# Preamp_Prueba.net
KiCad netlist of a schematic drawn in EAGLE
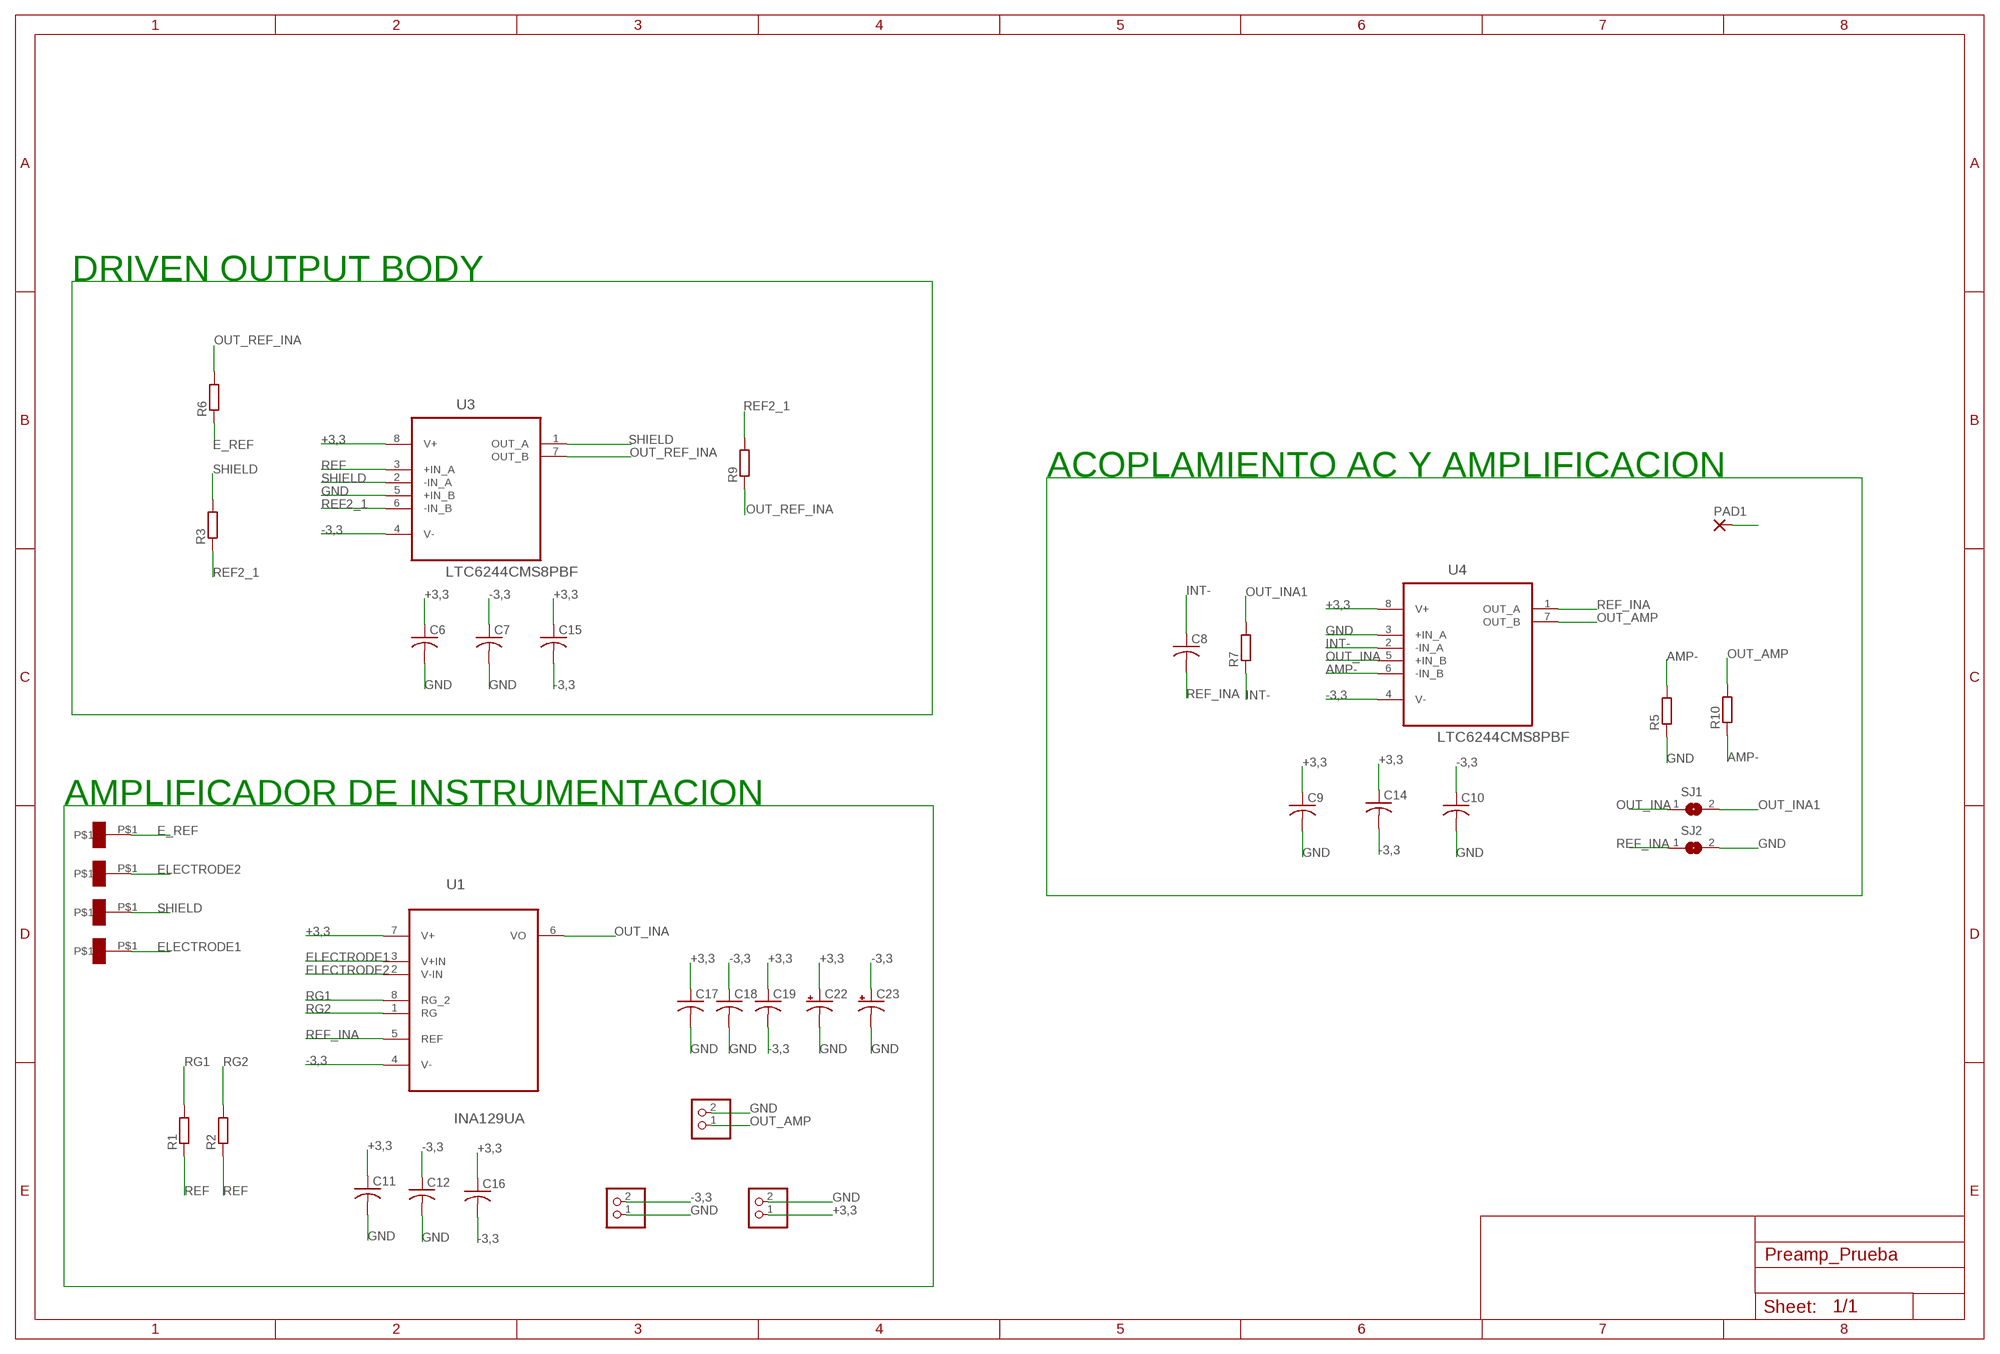
[diagram p0: schematic, sheet 1]

(export (version "E")
  (design (tool "Eeschema 10.0.6"))
  (components
    (comp (ref "C6")
      (value "C-USC0805")
      (footprint "eagle-import:C0805")
      (libsource (lib "eagle-import") (part "C-USC0805"))
    )
    (comp (ref "C7")
      (value "C-USC0805")
      (footprint "eagle-import:C0805")
      (libsource (lib "eagle-import") (part "C-USC0805"))
    )
    (comp (ref "C8")
      (value "C-USC0805")
      (footprint "eagle-import:C0805")
      (libsource (lib "eagle-import") (part "C-USC0805"))
    )
    (comp (ref "C9")
      (value "C-USC0805")
      (footprint "eagle-import:C0805")
      (libsource (lib "eagle-import") (part "C-USC0805"))
    )
    (comp (ref "C10")
      (value "C-USC0805")
      (footprint "eagle-import:C0805")
      (libsource (lib "eagle-import") (part "C-USC0805"))
    )
    (comp (ref "C11")
      (value "C-USC0805")
      (footprint "eagle-import:C0805")
      (libsource (lib "eagle-import") (part "C-USC0805"))
    )
    (comp (ref "C12")
      (value "C-USC0805")
      (footprint "eagle-import:C0805")
      (libsource (lib "eagle-import") (part "C-USC0805"))
    )
    (comp (ref "C14")
      (value "C-USC0805")
      (footprint "eagle-import:C0805")
      (libsource (lib "eagle-import") (part "C-USC0805"))
    )
    (comp (ref "C15")
      (value "C-USC0805")
      (footprint "eagle-import:C0805")
      (libsource (lib "eagle-import") (part "C-USC0805"))
    )
    (comp (ref "C16")
      (value "C-USC0805")
      (footprint "eagle-import:C0805")
      (libsource (lib "eagle-import") (part "C-USC0805"))
    )
    (comp (ref "C17")
      (value "C-USC0805")
      (footprint "eagle-import:C0805")
      (libsource (lib "eagle-import") (part "C-USC0805"))
    )
    (comp (ref "C18")
      (value "C-USC0805")
      (footprint "eagle-import:C0805")
      (libsource (lib "eagle-import") (part "C-USC0805"))
    )
    (comp (ref "C19")
      (value "C-USC0805")
      (footprint "eagle-import:C0805")
      (libsource (lib "eagle-import") (part "C-USC0805"))
    )
    (comp (ref "C22")
      (value "CPOL-USB/3528-21W")
      (footprint "eagle-import:B_3528-21W")
      (libsource (lib "eagle-import") (part "CPOL-USB/3528-21W"))
    )
    (comp (ref "C23")
      (value "CPOL-USB/3528-21W")
      (footprint "eagle-import:B_3528-21W")
      (libsource (lib "eagle-import") (part "CPOL-USB/3528-21W"))
    )
    (comp (ref "JP1")
      (value "PINHD-1X2")
      (footprint "eagle-import:1X02")
      (libsource (lib "eagle-import") (part "PINHD-1X2"))
    )
    (comp (ref "JP2")
      (value "PINHD-1X2")
      (footprint "eagle-import:1X02")
      (libsource (lib "eagle-import") (part "PINHD-1X2"))
    )
    (comp (ref "JP5")
      (value "PINHD-1X2")
      (footprint "eagle-import:1X02")
      (libsource (lib "eagle-import") (part "PINHD-1X2"))
    )
    (comp (ref "PAD1")
      (value "SMD2")
      (footprint "eagle-import:SMD1,27-2,54")
      (libsource (lib "eagle-import") (part "SMD2"))
    )
    (comp (ref "R1")
      (value "R-EU_R0805")
      (footprint "eagle-import:R0805")
      (libsource (lib "eagle-import") (part "R-EU_R0805"))
    )
    (comp (ref "R2")
      (value "R-EU_R0805")
      (footprint "eagle-import:R0805")
      (libsource (lib "eagle-import") (part "R-EU_R0805"))
    )
    (comp (ref "R3")
      (value "R-EU_R0805")
      (footprint "eagle-import:R0805")
      (libsource (lib "eagle-import") (part "R-EU_R0805"))
    )
    (comp (ref "R5")
      (value "R-EU_R0805")
      (footprint "eagle-import:R0805")
      (libsource (lib "eagle-import") (part "R-EU_R0805"))
    )
    (comp (ref "R6")
      (value "R-EU_R0805")
      (footprint "eagle-import:R0805")
      (libsource (lib "eagle-import") (part "R-EU_R0805"))
    )
    (comp (ref "R7")
      (value "R-EU_R0805")
      (footprint "eagle-import:R0805")
      (libsource (lib "eagle-import") (part "R-EU_R0805"))
    )
    (comp (ref "R9")
      (value "R-EU_R0805")
      (footprint "eagle-import:R0805")
      (libsource (lib "eagle-import") (part "R-EU_R0805"))
    )
    (comp (ref "R10")
      (value "R-EU_R0805")
      (footprint "eagle-import:R0805")
      (libsource (lib "eagle-import") (part "R-EU_R0805"))
    )
    (comp (ref "SJ1") (value "SJ") (footprint "eagle-import:SJ") (libsource (lib "eagle-import") (part "SJ")))
    (comp (ref "SJ2") (value "SJ") (footprint "eagle-import:SJ") (libsource (lib "eagle-import") (part "SJ")))
    (comp (ref "U$1")
      (value "PIN_E")
      (footprint "eagle-import:PIN")
      (libsource (lib "eagle-import") (part "PIN_E"))
    )
    (comp (ref "U$2")
      (value "PIN_E")
      (footprint "eagle-import:PIN")
      (libsource (lib "eagle-import") (part "PIN_E"))
    )
    (comp (ref "U$3")
      (value "PIN_E")
      (footprint "eagle-import:PIN")
      (libsource (lib "eagle-import") (part "PIN_E"))
    )
    (comp (ref "U$4")
      (value "PIN_E")
      (footprint "eagle-import:PIN")
      (libsource (lib "eagle-import") (part "PIN_E"))
    )
    (comp (ref "U1")
      (value "INA129UA")
      (footprint "eagle-import:SOIC127P600X175-8N")
      (fields (field (name "MF") "Texas Instruments"))
      (libsource (lib "eagle-import") (part "INA129UA"))
    )
    (comp (ref "U3")
      (value "LTC6244CMS8PBF")
      (footprint "eagle-import:SOP65P490X110-8N")
      (fields (field (name "MF") "Linear Technology") (field (name "MP") "LTC6244CMS8#PBF"))
      (libsource (lib "eagle-import") (part "LTC6244CMS8PBF"))
    )
    (comp (ref "U4")
      (value "LTC6244CMS8PBF")
      (footprint "eagle-import:SOP65P490X110-8N")
      (fields (field (name "MF") "Linear Technology") (field (name "MP") "LTC6244CMS8#PBF"))
      (libsource (lib "eagle-import") (part "LTC6244CMS8PBF"))
    )
  )
  (nets
    (net (code "1") (name "/+3,3") (class "Default")
      (node (ref "C11") (pin "1") (pinfunction "1_1") (pintype "passive"))
      (node (ref "C14") (pin "1") (pinfunction "1_1") (pintype "passive"))
      (node (ref "C15") (pin "1") (pinfunction "1_1") (pintype "passive"))
      (node (ref "C16") (pin "1") (pinfunction "1_1") (pintype "passive"))
      (node (ref "C17") (pin "1") (pinfunction "1_1") (pintype "passive"))
      (node (ref "C19") (pin "1") (pinfunction "1_1") (pintype "passive"))
      (node (ref "C22") (pin "+") (pinfunction "+_+") (pintype "passive"))
      (node (ref "C6") (pin "1") (pinfunction "1_1") (pintype "passive"))
      (node (ref "C9") (pin "1") (pinfunction "1_1") (pintype "passive"))
      (node (ref "JP2") (pin "1") (pinfunction "1_1") (pintype "passive"))
      (node (ref "U1") (pin "7") (pinfunction "V+_7") (pintype "power_in"))
      (node (ref "U3") (pin "8") (pinfunction "V+_8") (pintype "power_in"))
      (node (ref "U4") (pin "8") (pinfunction "V+_8") (pintype "power_in"))
    )
    (net (code "2") (name "/-3,3") (class "Default")
      (node (ref "C10") (pin "1") (pinfunction "1_1") (pintype "passive"))
      (node (ref "C12") (pin "1") (pinfunction "1_1") (pintype "passive"))
      (node (ref "C14") (pin "2") (pinfunction "2_2") (pintype "passive"))
      (node (ref "C15") (pin "2") (pinfunction "2_2") (pintype "passive"))
      (node (ref "C16") (pin "2") (pinfunction "2_2") (pintype "passive"))
      (node (ref "C18") (pin "1") (pinfunction "1_1") (pintype "passive"))
      (node (ref "C19") (pin "2") (pinfunction "2_2") (pintype "passive"))
      (node (ref "C23") (pin "+") (pinfunction "+_+") (pintype "passive"))
      (node (ref "C7") (pin "1") (pinfunction "1_1") (pintype "passive"))
      (node (ref "JP1") (pin "2") (pinfunction "2_2") (pintype "passive"))
      (node (ref "U1") (pin "4") (pinfunction "V-_4") (pintype "power_in"))
      (node (ref "U3") (pin "4") (pinfunction "V-_4") (pintype "power_in"))
      (node (ref "U4") (pin "4") (pinfunction "V-_4") (pintype "power_in"))
    )
    (net (code "3") (name "/AMP-") (class "Default")
      (node (ref "R10") (pin "1") (pinfunction "1_1") (pintype "passive"))
      (node (ref "R5") (pin "2") (pinfunction "2_2") (pintype "passive"))
      (node (ref "U4") (pin "6") (pinfunction "-IN_B_6") (pintype "input"))
    )
    (net (code "4") (name "/ELECTRODE1") (class "Default")
      (node (ref "U$4") (pin "P$1") (pinfunction "P$1_P$1") (pintype "bidirectional"))
      (node (ref "U1") (pin "3") (pinfunction "V+IN_3") (pintype "input"))
    )
    (net (code "5") (name "/ELECTRODE2") (class "Default")
      (node (ref "U$2") (pin "P$1") (pinfunction "P$1_P$1") (pintype "bidirectional"))
      (node (ref "U1") (pin "2") (pinfunction "V-IN_2") (pintype "input"))
    )
    (net (code "6") (name "/E_REF") (class "Default")
      (node (ref "R6") (pin "1") (pinfunction "1_1") (pintype "passive"))
      (node (ref "U$3") (pin "P$1") (pinfunction "P$1_P$1") (pintype "bidirectional"))
    )
    (net (code "7") (name "/GND") (class "Default")
      (node (ref "C10") (pin "2") (pinfunction "2_2") (pintype "passive"))
      (node (ref "C11") (pin "2") (pinfunction "2_2") (pintype "passive"))
      (node (ref "C12") (pin "2") (pinfunction "2_2") (pintype "passive"))
      (node (ref "C17") (pin "2") (pinfunction "2_2") (pintype "passive"))
      (node (ref "C18") (pin "2") (pinfunction "2_2") (pintype "passive"))
      (node (ref "C22") (pin "-") (pinfunction "-_-") (pintype "passive"))
      (node (ref "C23") (pin "-") (pinfunction "-_-") (pintype "passive"))
      (node (ref "C6") (pin "2") (pinfunction "2_2") (pintype "passive"))
      (node (ref "C7") (pin "2") (pinfunction "2_2") (pintype "passive"))
      (node (ref "C9") (pin "2") (pinfunction "2_2") (pintype "passive"))
      (node (ref "JP1") (pin "1") (pinfunction "1_1") (pintype "passive"))
      (node (ref "JP2") (pin "2") (pinfunction "2_2") (pintype "passive"))
      (node (ref "JP5") (pin "2") (pinfunction "2_2") (pintype "passive"))
      (node (ref "PAD1") (pin "1") (pinfunction "P_1") (pintype "passive"))
      (node (ref "R5") (pin "1") (pinfunction "1_1") (pintype "passive"))
      (node (ref "SJ2") (pin "2") (pinfunction "2_2") (pintype "passive"))
      (node (ref "U3") (pin "5") (pinfunction "+IN_B_5") (pintype "input"))
      (node (ref "U4") (pin "3") (pinfunction "+IN_A_3") (pintype "input"))
    )
    (net (code "8") (name "/INT-") (class "Default")
      (node (ref "C8") (pin "1") (pinfunction "1_1") (pintype "passive"))
      (node (ref "R7") (pin "1") (pinfunction "1_1") (pintype "passive"))
      (node (ref "U4") (pin "2") (pinfunction "-IN_A_2") (pintype "input"))
    )
    (net (code "9") (name "/OUT_AMP") (class "Default")
      (node (ref "JP5") (pin "1") (pinfunction "1_1") (pintype "passive"))
      (node (ref "R10") (pin "2") (pinfunction "2_2") (pintype "passive"))
      (node (ref "U4") (pin "7") (pinfunction "OUT_B_7") (pintype "output"))
    )
    (net (code "10") (name "/OUT_INA") (class "Default")
      (node (ref "SJ1") (pin "1") (pinfunction "1_1") (pintype "passive"))
      (node (ref "U1") (pin "6") (pinfunction "VO_6") (pintype "output"))
      (node (ref "U4") (pin "5") (pinfunction "+IN_B_5") (pintype "input"))
    )
    (net (code "11") (name "/OUT_INA1") (class "Default")
      (node (ref "R7") (pin "2") (pinfunction "2_2") (pintype "passive"))
      (node (ref "SJ1") (pin "2") (pinfunction "2_2") (pintype "passive"))
    )
    (net (code "12") (name "/OUT_REF_INA") (class "Default")
      (node (ref "R6") (pin "2") (pinfunction "2_2") (pintype "passive"))
      (node (ref "R9") (pin "1") (pinfunction "1_1") (pintype "passive"))
      (node (ref "U3") (pin "7") (pinfunction "OUT_B_7") (pintype "output"))
    )
    (net (code "13") (name "/REF") (class "Default")
      (node (ref "R1") (pin "1") (pinfunction "1_1") (pintype "passive"))
      (node (ref "R2") (pin "1") (pinfunction "1_1") (pintype "passive"))
      (node (ref "U3") (pin "3") (pinfunction "+IN_A_3") (pintype "input"))
    )
    (net (code "14") (name "/REF2_1") (class "Default")
      (node (ref "R3") (pin "1") (pinfunction "1_1") (pintype "passive"))
      (node (ref "R9") (pin "2") (pinfunction "2_2") (pintype "passive"))
      (node (ref "U3") (pin "6") (pinfunction "-IN_B_6") (pintype "input"))
    )
    (net (code "15") (name "/REF_INA") (class "Default")
      (node (ref "C8") (pin "2") (pinfunction "2_2") (pintype "passive"))
      (node (ref "SJ2") (pin "1") (pinfunction "1_1") (pintype "passive"))
      (node (ref "U1") (pin "5") (pinfunction "REF_5") (pintype "input"))
      (node (ref "U4") (pin "1") (pinfunction "OUT_A_1") (pintype "output"))
    )
    (net (code "16") (name "/RG1") (class "Default")
      (node (ref "R1") (pin "2") (pinfunction "2_2") (pintype "passive"))
      (node (ref "U1") (pin "8") (pinfunction "RG_2_8") (pintype "input"))
    )
    (net (code "17") (name "/RG2") (class "Default")
      (node (ref "R2") (pin "2") (pinfunction "2_2") (pintype "passive"))
      (node (ref "U1") (pin "1") (pinfunction "RG_1") (pintype "input"))
    )
    (net (code "18") (name "/SHIELD") (class "Default")
      (node (ref "R3") (pin "2") (pinfunction "2_2") (pintype "passive"))
      (node (ref "U$1") (pin "P$1") (pinfunction "P$1_P$1") (pintype "bidirectional"))
      (node (ref "U3") (pin "1") (pinfunction "OUT_A_1") (pintype "output"))
      (node (ref "U3") (pin "2") (pinfunction "-IN_A_2") (pintype "input"))
    )
  )
)
